# DRV8825_SHIELD.net
KiCad netlist of a schematic drawn in EAGLE
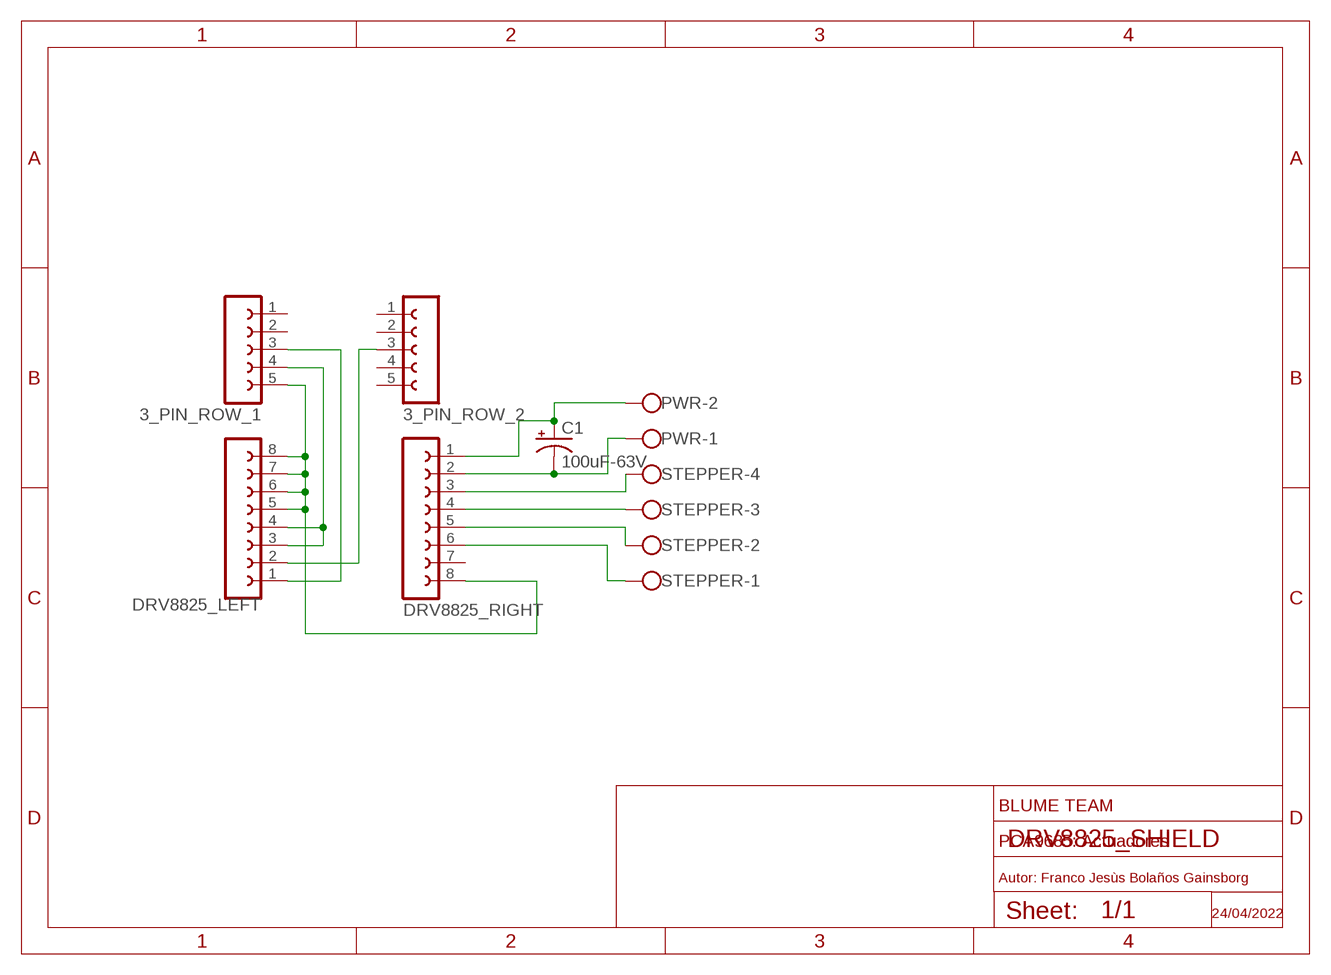
[diagram p0: schematic, sheet 1]

(export (version "E")
  (design (tool "Eeschema 10.0.6"))
  (components
    (comp (ref "3_PIN_ROW_1")
      (value "FE05-1")
      (footprint "eagle-import:FE05-1")
      (libsource (lib "eagle-import") (part "FE05-1"))
    )
    (comp (ref "3_PIN_ROW_2")
      (value "FE05-1")
      (footprint "eagle-import:FE05-1")
      (libsource (lib "eagle-import") (part "FE05-1"))
    )
    (comp (ref "C1")
      (value "100uF-63V")
      (footprint "eagle-import:E5-10,5")
      (libsource (lib "eagle-import") (part "CPOL-USE5-10.5"))
    )
    (comp (ref "DRV8825_LEFT")
      (value "FE08-1")
      (footprint "eagle-import:FE08")
      (libsource (lib "eagle-import") (part "FE08-1"))
    )
    (comp (ref "DRV8825_RIGHT")
      (value "FE08-1")
      (footprint "eagle-import:FE08")
      (libsource (lib "eagle-import") (part "FE08-1"))
    )
    (comp (ref "PWR")
      (value "W237-102")
      (footprint "eagle-import:W237-102")
      (fields (field (name "MPN") "237-102"))
      (libsource (lib "eagle-import") (part "W237-102"))
    )
    (comp (ref "STEPPER")
      (value "W237-4")
      (footprint "eagle-import:W237-4")
      (libsource (lib "eagle-import") (part "W237-4"))
    )
  )
  (nets
    (net (code "1") (name "Net-(3_PIN_ROW_1-Pad3)") (class "Default")
      (node (ref "3_PIN_ROW_1") (pin "3") (pinfunction "3_3") (pintype "passive"))
      (node (ref "DRV8825_LEFT") (pin "1") (pinfunction "1_1") (pintype "passive"))
    )
    (net (code "2") (name "Net-(3_PIN_ROW_1-Pad4)") (class "Default")
      (node (ref "3_PIN_ROW_1") (pin "4") (pinfunction "4_4") (pintype "passive"))
      (node (ref "DRV8825_LEFT") (pin "3") (pinfunction "3_3") (pintype "passive"))
      (node (ref "DRV8825_LEFT") (pin "4") (pinfunction "4_4") (pintype "passive"))
    )
    (net (code "3") (name "Net-(3_PIN_ROW_1-Pad5)") (class "Default")
      (node (ref "3_PIN_ROW_1") (pin "5") (pinfunction "5_5") (pintype "passive"))
      (node (ref "DRV8825_LEFT") (pin "5") (pinfunction "5_5") (pintype "passive"))
      (node (ref "DRV8825_LEFT") (pin "6") (pinfunction "6_6") (pintype "passive"))
      (node (ref "DRV8825_LEFT") (pin "7") (pinfunction "7_7") (pintype "passive"))
      (node (ref "DRV8825_LEFT") (pin "8") (pinfunction "8_8") (pintype "passive"))
      (node (ref "DRV8825_RIGHT") (pin "8") (pinfunction "8_8") (pintype "passive"))
    )
    (net (code "4") (name "Net-(3_PIN_ROW_2-Pad3)") (class "Default")
      (node (ref "3_PIN_ROW_2") (pin "3") (pinfunction "3_3") (pintype "passive"))
      (node (ref "DRV8825_LEFT") (pin "2") (pinfunction "2_2") (pintype "passive"))
    )
    (net (code "5") (name "Net-(PWRA-KL)") (class "Default")
      (node (ref "C1") (pin "-") (pinfunction "-_-") (pintype "passive"))
      (node (ref "DRV8825_RIGHT") (pin "2") (pinfunction "2_2") (pintype "passive"))
      (node (ref "PWR") (pin "1") (pinfunction "KL_1") (pintype "passive"))
    )
    (net (code "6") (name "Net-(PWRB-KL)") (class "Default")
      (node (ref "C1") (pin "+") (pinfunction "+_+") (pintype "passive"))
      (node (ref "DRV8825_RIGHT") (pin "1") (pinfunction "1_1") (pintype "passive"))
      (node (ref "PWR") (pin "2") (pinfunction "KL_2") (pintype "passive"))
    )
    (net (code "7") (name "Net-(STEPPERA-KL)") (class "Default")
      (node (ref "DRV8825_RIGHT") (pin "6") (pinfunction "6_6") (pintype "passive"))
      (node (ref "STEPPER") (pin "1") (pinfunction "KL_1") (pintype "passive"))
    )
    (net (code "8") (name "Net-(STEPPERB-KL)") (class "Default")
      (node (ref "DRV8825_RIGHT") (pin "5") (pinfunction "5_5") (pintype "passive"))
      (node (ref "STEPPER") (pin "2") (pinfunction "KL_2") (pintype "passive"))
    )
    (net (code "9") (name "Net-(STEPPERC-KL)") (class "Default")
      (node (ref "DRV8825_RIGHT") (pin "4") (pinfunction "4_4") (pintype "passive"))
      (node (ref "STEPPER") (pin "3") (pinfunction "KL_3") (pintype "passive"))
    )
    (net (code "10") (name "Net-(STEPPERD-KL)") (class "Default")
      (node (ref "DRV8825_RIGHT") (pin "3") (pinfunction "3_3") (pintype "passive"))
      (node (ref "STEPPER") (pin "4") (pinfunction "KL_4") (pintype "passive"))
    )
    (net (code "11") (name "unconnected-(3_PIN_ROW_1-Pad1)") (class "Default")
      (node (ref "3_PIN_ROW_1") (pin "1") (pinfunction "1_1") (pintype "passive"))
    )
    (net (code "12") (name "unconnected-(3_PIN_ROW_1-Pad2)") (class "Default")
      (node (ref "3_PIN_ROW_1") (pin "2") (pinfunction "2_2") (pintype "passive"))
    )
    (net (code "13") (name "unconnected-(3_PIN_ROW_2-Pad1)") (class "Default")
      (node (ref "3_PIN_ROW_2") (pin "1") (pinfunction "1_1") (pintype "passive"))
    )
    (net (code "14") (name "unconnected-(3_PIN_ROW_2-Pad2)") (class "Default")
      (node (ref "3_PIN_ROW_2") (pin "2") (pinfunction "2_2") (pintype "passive"))
    )
    (net (code "15") (name "unconnected-(3_PIN_ROW_2-Pad4)") (class "Default")
      (node (ref "3_PIN_ROW_2") (pin "4") (pinfunction "4_4") (pintype "passive"))
    )
    (net (code "16") (name "unconnected-(3_PIN_ROW_2-Pad5)") (class "Default")
      (node (ref "3_PIN_ROW_2") (pin "5") (pinfunction "5_5") (pintype "passive"))
    )
    (net (code "17") (name "unconnected-(DRV8825_RIGHT-Pad7)") (class "Default")
      (node (ref "DRV8825_RIGHT") (pin "7") (pinfunction "7_7") (pintype "passive"))
    )
  )
)
